# System.net
KiCad netlist of a schematic drawn in Altium Designer
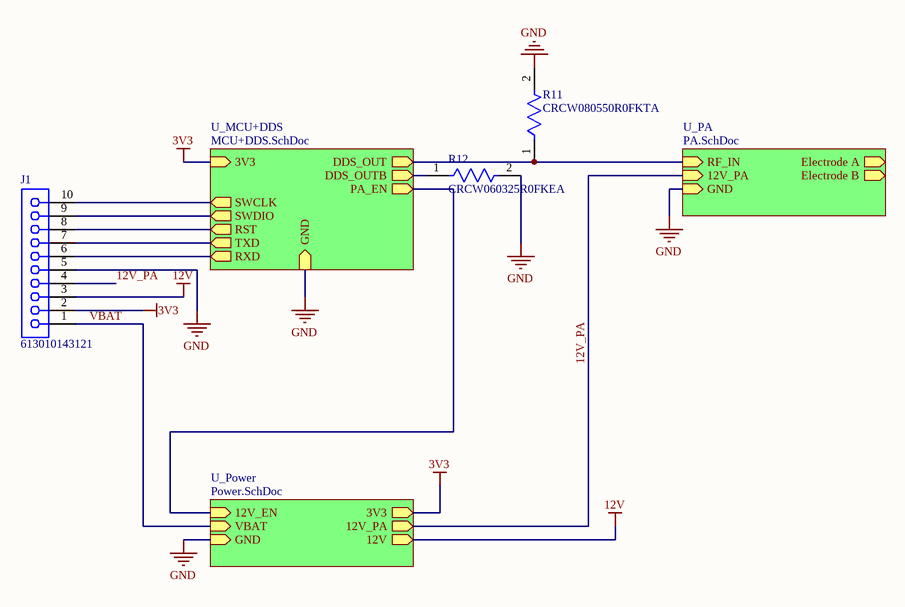
[diagram p0: System.SchDoc]

(export (version "E")
  (design (tool "Eeschema 10.0.6"))
  (components
    (comp (ref "J1")
      (value "613010143121")
      (footprint "613010143121")
      (libsource (lib "Altium Content Vault") (part "Header_Female_1R_10P"))
    )
    (comp (ref "R11")
      (value "CRCW080550R0FKTA")
      (footprint "FP-D12-CRCW0805-MFG")
      (description "CRCW080550R0FKTA Res Thick Film 0805 50 Ohm 1% 0.125W(1/8W) ±100ppm/C Pad SMD Automotive T/R")
      (fields (field (name "TOLERANCE") "1%"))
      (libsource (lib "Altium Content Vault") (part "1029c3af85768c4190bb7ad29bc67b5"))
    )
    (comp (ref "R12")
      (value "CRCW060325R0FKEA")
      (footprint "FP-CRCW0603-e3-IPC_B")
      (description "RES Thick Film, 25Ω, 1%, 0.1W, 100ppm/°C, 0603")
      (fields (field (name "TOLERANCE") "1%"))
      (libsource (lib "Altium Content Vault") (part "1029c3af85768c4190bb7ad29bc67b5"))
    )
  )
  (nets
    (net (code "1") (name "/12V_PA") (class "Default")
      (node (ref "J1") (pin "4") (pinfunction "4_4") (pintype "passive"))
    )
    (net (code "2") (name "/DDS_OUT") (class "Default")
      (node (ref "R11") (pin "1") (pinfunction "1_1") (pintype "passive"))
    )
    (net (code "3") (name "/DDS_OUTB") (class "Default")
      (node (ref "R12") (pin "1") (pinfunction "1_1") (pintype "passive"))
    )
    (net (code "7") (name "/RST") (class "Default")
      (node (ref "J1") (pin "8") (pinfunction "8_8") (pintype "passive"))
    )
    (net (code "8") (name "/RXD") (class "Default")
      (node (ref "J1") (pin "6") (pinfunction "6_6") (pintype "passive"))
    )
    (net (code "9") (name "/SWCLK") (class "Default")
      (node (ref "J1") (pin "10") (pinfunction "10_10") (pintype "passive"))
    )
    (net (code "10") (name "/SWDIO") (class "Default")
      (node (ref "J1") (pin "9") (pinfunction "9_9") (pintype "passive"))
    )
    (net (code "11") (name "/TXD") (class "Default")
      (node (ref "J1") (pin "7") (pinfunction "7_7") (pintype "passive"))
    )
    (net (code "12") (name "/VBAT") (class "Default")
      (node (ref "J1") (pin "1") (pinfunction "1_1") (pintype "passive"))
    )
    (net (code "13") (name "3V3") (class "Default")
      (node (ref "J1") (pin "2") (pinfunction "2_2") (pintype "passive"))
    )
    (net (code "14") (name "12V") (class "Default")
      (node (ref "J1") (pin "3") (pinfunction "3_3") (pintype "passive"))
    )
    (net (code "15") (name "GND") (class "Default")
      (node (ref "J1") (pin "5") (pinfunction "5_5") (pintype "passive"))
      (node (ref "R11") (pin "2") (pinfunction "2_2") (pintype "passive"))
      (node (ref "R12") (pin "2") (pinfunction "2_2") (pintype "passive"))
    )
  )
)
